# MCU.net
KiCad netlist of a schematic drawn in Altium Designer
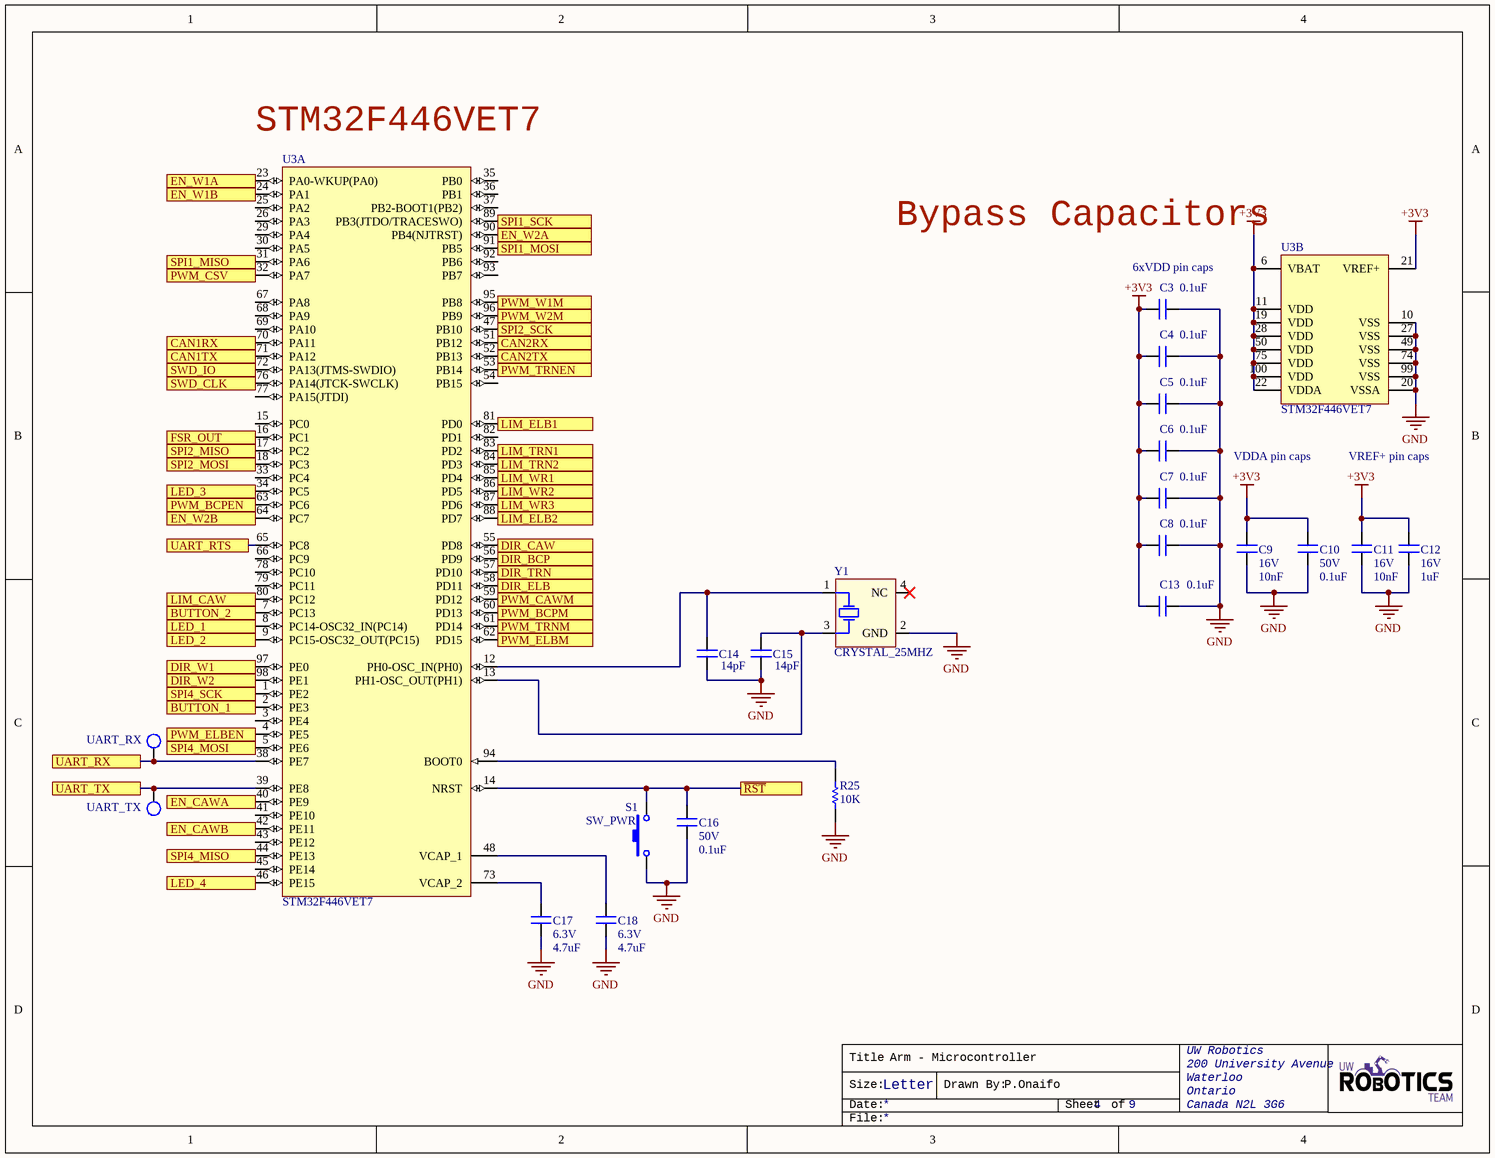
[diagram p0: MCU.SchDoc]

(export (version "E")
  (design (tool "Eeschema 10.0.6"))
  (components
    (comp (ref "C3")
      (value "0.1uF")
      (footprint "CAPC0603(1608)55_N")
      (description "CAP CER 0.1UF 50V X7R 0603")
      (fields (field (name "MPN") "CC0603KRX7R9BB104") (field (name "MANUFACTURER") "Yageo"))
      (libsource (lib "UWRT_Schematic_Library_2020") (part "CAP_0.1uF_50V_0603"))
    )
    (comp (ref "C4")
      (value "0.1uF")
      (footprint "CAPC0603(1608)55_N")
      (description "CAP CER 0.1UF 50V X7R 0603")
      (fields (field (name "MPN") "CC0603KRX7R9BB104") (field (name "MANUFACTURER") "Yageo"))
      (libsource (lib "UWRT_Schematic_Library_2020") (part "CAP_0.1uF_50V_0603"))
    )
    (comp (ref "C5")
      (value "0.1uF")
      (footprint "CAPC0603(1608)55_N")
      (description "CAP CER 0.1UF 50V X7R 0603")
      (fields (field (name "MPN") "CC0603KRX7R9BB104") (field (name "MANUFACTURER") "Yageo"))
      (libsource (lib "UWRT_Schematic_Library_2020") (part "CAP_0.1uF_50V_0603"))
    )
    (comp (ref "C6")
      (value "0.1uF")
      (footprint "CAPC0603(1608)55_N")
      (description "CAP CER 0.1UF 50V X7R 0603")
      (fields (field (name "MPN") "CC0603KRX7R9BB104") (field (name "MANUFACTURER") "Yageo"))
      (libsource (lib "UWRT_Schematic_Library_2020") (part "CAP_0.1uF_50V_0603"))
    )
    (comp (ref "C7")
      (value "0.1uF")
      (footprint "CAPC0603(1608)55_N")
      (description "CAP CER 0.1UF 50V X7R 0603")
      (fields (field (name "MPN") "CC0603KRX7R9BB104") (field (name "MANUFACTURER") "Yageo"))
      (libsource (lib "UWRT_Schematic_Library_2020") (part "CAP_0.1uF_50V_0603"))
    )
    (comp (ref "C8")
      (value "0.1uF")
      (footprint "CAPC0603(1608)55_N")
      (description "CAP CER 0.1UF 50V X7R 0603")
      (fields (field (name "MPN") "CC0603KRX7R9BB104") (field (name "MANUFACTURER") "Yageo"))
      (libsource (lib "UWRT_Schematic_Library_2020") (part "CAP_0.1uF_50V_0603"))
    )
    (comp (ref "C9")
      (value "10nF")
      (footprint "CAPC0603(1608)55_N")
      (description "CAP CER 10000PF 16V X7R 0603")
      (fields
        (field (name "MPN") "CC0603KRX7R7BB103")
        (field (name "MANUFACTURER") "Yageo")
        (field (name "VOLTAGE RATING") "16V")
      )
      (libsource (lib "UWRT_Schematic_Library_2020") (part "CAP_10nF_0603"))
    )
    (comp (ref "C10")
      (value "0.1uF")
      (footprint "CAPC0603(1608)55_N")
      (description "CAP CER 0.1UF 50V X7R 0603")
      (fields
        (field (name "MPN") "CC0603KRX7R9BB104")
        (field (name "MANUFACTURER") "Yageo")
        (field (name "VOLTAGE RATING") "50V")
      )
      (libsource (lib "UWRT_Schematic_Library_2020") (part "CAP_0.1uF_50V_0603"))
    )
    (comp (ref "C11")
      (value "10nF")
      (footprint "CAPC0603(1608)55_N")
      (description "CAP CER 10000PF 16V X7R 0603")
      (fields
        (field (name "MPN") "CC0603KRX7R7BB103")
        (field (name "MANUFACTURER") "Yageo")
        (field (name "VOLTAGE RATING") "16V")
      )
      (libsource (lib "UWRT_Schematic_Library_2020") (part "CAP_10nF_0603"))
    )
    (comp (ref "C12")
      (value "1uF")
      (footprint "CAPC0603(1608)55_N")
      (description "CAP CER 1UF 16V Y5V 0603")
      (fields
        (field (name "MPN") "CC0603ZRY5V7BB105")
        (field (name "MANUFACTURER") "Yageo")
        (field (name "VOLTAGE RATING") "16V")
      )
      (libsource (lib "UWRT_Schematic_Library_2020") (part "CAP_1uF_16V_0603"))
    )
    (comp (ref "C13")
      (value "0.1uF")
      (footprint "CAPC0603(1608)55_N")
      (description "CAP CER 0.1UF 50V X7R 0603")
      (fields (field (name "MPN") "CC0603KRX7R9BB104") (field (name "MANUFACTURER") "Yageo"))
      (libsource (lib "UWRT_Schematic_Library_2020") (part "CAP_0.1uF_50V_0603"))
    )
    (comp (ref "C14")
      (value "14pF")
      (description "CAP CER 14PF 50V C0G/NP0 0603")
      (fields (field (name "TOLERANCE") "5%") (field (name "Comment") "CAP_14pF_50V_0603"))
      (libsource (lib "UWRT_Schematic_Library_2020") (part "CAP_14pF_50V_0603"))
    )
    (comp (ref "C15")
      (value "14pF")
      (description "CAP CER 14PF 50V C0G/NP0 0603")
      (fields (field (name "TOLERANCE") "5%") (field (name "Comment") "CAP_14pF_50V_0603"))
      (libsource (lib "UWRT_Schematic_Library_2020") (part "CAP_14pF_50V_0603"))
    )
    (comp (ref "C16")
      (value "0.1uF")
      (footprint "CAPC0603(1608)55_N")
      (description "CAP CER 0.1UF 50V X7R 0603")
      (fields
        (field (name "MPN") "CC0603KRX7R9BB104")
        (field (name "MANUFACTURER") "Yageo")
        (field (name "VOLTAGE RATING") "50V")
      )
      (libsource (lib "UWRT_Schematic_Library_2020") (part "CAP_0.1uF_50V_0603"))
    )
    (comp (ref "C17")
      (value "4.7uF")
      (footprint "CAPC0603(1608)55_N")
      (description "CAP CER 4.7UF 6.3V X5R 0603")
      (fields
        (field (name "MPN") "CC0603KRX5R5BB475")
        (field (name "MANUFACTURER") "Yageo")
        (field (name "VOLTAGE RATING") "6.3V")
      )
      (libsource (lib "UWRT_Schematic_Library_2020") (part "CAP_4.7uF_0603"))
    )
    (comp (ref "C18")
      (value "4.7uF")
      (footprint "CAPC0603(1608)55_N")
      (description "CAP CER 4.7UF 6.3V X5R 0603")
      (fields
        (field (name "MPN") "CC0603KRX5R5BB475")
        (field (name "MANUFACTURER") "Yageo")
        (field (name "VOLTAGE RATING") "6.3V")
      )
      (libsource (lib "UWRT_Schematic_Library_2020") (part "CAP_4.7uF_0603"))
    )
    (comp (ref "R25")
      (value "10K")
      (footprint "RESC0603(1608)_N")
      (description "RES SMD 10K OHM 5% 1/10W 0603")
      (fields (field (name "MANUFACTURER") "Yageo") (field (name "MPN") "RC0603JR-0710KL"))
      (libsource (lib "UWRT_Schematic_Library_2020") (part "RES_10K_0603"))
    )
    (comp (ref "S1")
      (value "SW_PWR")
      (footprint "PTS830GM140")
      (description "Power Switch (Red)")
      (fields (field (name "MPN") "PTS830GM140 SMTR LFS") (field (name "MANUFACTURER") "C&K"))
      (libsource (lib "UWRT_Schematic_Library_2020") (part "SW_PWR"))
    )
    (comp (ref "U3")
      (value "STM32F446VET7")
      (footprint "STM-LQFP100_L")
      (libsource (lib "Altium Content Vault") (part "MC-ARM-STM32F446-LQFP100"))
    )
    (comp (ref "UART_RX")
      (value "TESTPOINT_LOOP")
      (footprint "TESTPOINT_LOOP")
      (description "Loop testpoint through-hole pad")
      (fields (field (name "MANUFACTURER") "Keystone Electronics"))
      (libsource (lib "UWRT_Schematic_Library_2020") (part "TESTPOINT_LOOP"))
    )
    (comp (ref "UART_TX")
      (value "TESTPOINT_LOOP")
      (footprint "TESTPOINT_LOOP")
      (description "Loop testpoint through-hole pad")
      (fields (field (name "MANUFACTURER") "Keystone Electronics"))
      (libsource (lib "UWRT_Schematic_Library_2020") (part "TESTPOINT_LOOP"))
    )
    (comp (ref "Y1")
      (value "CRYSTAL_25MHZ")
      (description "CRYSTAL 25.0000MHZ 12PF SMD")
      (libsource (lib "UWRT_Schematic_Library_2020") (part "CRYSTAL_25MHZ"))
    )
  )
  (nets
    (net (code "1") (name "+3V3") (class "Default")
      (node (ref "C10") (pin "2") (pinfunction "2_2") (pintype "passive"))
      (node (ref "C11") (pin "1") (pinfunction "1_1") (pintype "passive"))
      (node (ref "C12") (pin "2") (pinfunction "2_2") (pintype "passive"))
      (node (ref "C13") (pin "1") (pinfunction "1_1") (pintype "passive"))
      (node (ref "C3") (pin "1") (pinfunction "1_1") (pintype "passive"))
      (node (ref "C4") (pin "1") (pinfunction "1_1") (pintype "passive"))
      (node (ref "C5") (pin "1") (pinfunction "1_1") (pintype "passive"))
      (node (ref "C6") (pin "1") (pinfunction "1_1") (pintype "passive"))
      (node (ref "C7") (pin "1") (pinfunction "1_1") (pintype "passive"))
      (node (ref "C8") (pin "1") (pinfunction "1_1") (pintype "passive"))
      (node (ref "C9") (pin "2") (pinfunction "2_2") (pintype "passive"))
      (node (ref "U3") (pin "100") (pinfunction "VDD_100") (pintype "power_in"))
      (node (ref "U3") (pin "11") (pinfunction "VDD_11") (pintype "power_in"))
      (node (ref "U3") (pin "19") (pinfunction "VDD_19") (pintype "power_in"))
      (node (ref "U3") (pin "21") (pinfunction "VREF+_21") (pintype "power_in"))
      (node (ref "U3") (pin "22") (pinfunction "VDDA_22") (pintype "power_in"))
      (node (ref "U3") (pin "28") (pinfunction "VDD_28") (pintype "power_in"))
      (node (ref "U3") (pin "50") (pinfunction "VDD_50") (pintype "power_in"))
      (node (ref "U3") (pin "6") (pinfunction "VBAT_6") (pintype "power_in"))
      (node (ref "U3") (pin "75") (pinfunction "VDD_75") (pintype "power_in"))
    )
    (net (code "2") (name "/BUTTON_1") (class "Default")
      (node (ref "U3") (pin "2") (pinfunction "PE3_2") (pintype "bidirectional"))
    )
    (net (code "3") (name "/BUTTON_2") (class "Default")
      (node (ref "U3") (pin "7") (pinfunction "PC13_7") (pintype "bidirectional"))
    )
    (net (code "4") (name "/CAN1RX") (class "Default")
      (node (ref "U3") (pin "70") (pinfunction "PA11_70") (pintype "bidirectional"))
    )
    (net (code "5") (name "/CAN1TX") (class "Default")
      (node (ref "U3") (pin "71") (pinfunction "PA12_71") (pintype "bidirectional"))
    )
    (net (code "6") (name "/CAN2RX") (class "Default")
      (node (ref "U3") (pin "51") (pinfunction "PB12_51") (pintype "bidirectional"))
    )
    (net (code "7") (name "/CAN2TX") (class "Default")
      (node (ref "U3") (pin "52") (pinfunction "PB13_52") (pintype "bidirectional"))
    )
    (net (code "8") (name "/DIR_BCP") (class "Default")
      (node (ref "U3") (pin "56") (pinfunction "PD9_56") (pintype "bidirectional"))
    )
    (net (code "9") (name "/DIR_CAW") (class "Default")
      (node (ref "U3") (pin "55") (pinfunction "PD8_55") (pintype "bidirectional"))
    )
    (net (code "10") (name "/DIR_ELB") (class "Default")
      (node (ref "U3") (pin "58") (pinfunction "PD11_58") (pintype "bidirectional"))
    )
    (net (code "11") (name "/DIR_TRN") (class "Default")
      (node (ref "U3") (pin "57") (pinfunction "PD10_57") (pintype "bidirectional"))
    )
    (net (code "12") (name "/DIR_W1") (class "Default")
      (node (ref "U3") (pin "97") (pinfunction "PE0_97") (pintype "bidirectional"))
    )
    (net (code "13") (name "/DIR_W2") (class "Default")
      (node (ref "U3") (pin "98") (pinfunction "PE1_98") (pintype "bidirectional"))
    )
    (net (code "14") (name "/EN_CAWA") (class "Default")
      (node (ref "U3") (pin "40") (pinfunction "PE9_40") (pintype "bidirectional"))
    )
    (net (code "15") (name "/EN_CAWB") (class "Default")
      (node (ref "U3") (pin "42") (pinfunction "PE11_42") (pintype "bidirectional"))
    )
    (net (code "16") (name "/EN_W1A") (class "Default")
      (node (ref "U3") (pin "23") (pinfunction "PA0-WKUP(PA0)_23") (pintype "bidirectional"))
    )
    (net (code "17") (name "/EN_W1B") (class "Default")
      (node (ref "U3") (pin "24") (pinfunction "PA1_24") (pintype "bidirectional"))
    )
    (net (code "18") (name "/EN_W2A") (class "Default")
      (node (ref "U3") (pin "90") (pinfunction "PB4(NJTRST)_90") (pintype "bidirectional"))
    )
    (net (code "19") (name "/EN_W2B") (class "Default")
      (node (ref "U3") (pin "64") (pinfunction "PC7_64") (pintype "bidirectional"))
    )
    (net (code "20") (name "/FSR_OUT") (class "Default")
      (node (ref "U3") (pin "16") (pinfunction "PC1_16") (pintype "bidirectional"))
    )
    (net (code "21") (name "/LED_1") (class "Default")
      (node (ref "U3") (pin "8") (pinfunction "PC14-OSC32_IN(PC14)_8") (pintype "bidirectional"))
    )
    (net (code "22") (name "/LED_2") (class "Default")
      (node (ref "U3") (pin "9") (pinfunction "PC15-OSC32_OUT(PC15)_9") (pintype "bidirectional"))
    )
    (net (code "23") (name "/LED_3") (class "Default")
      (node (ref "U3") (pin "34") (pinfunction "PC5_34") (pintype "bidirectional"))
    )
    (net (code "24") (name "/LED_4") (class "Default")
      (node (ref "U3") (pin "46") (pinfunction "PE15_46") (pintype "bidirectional"))
    )
    (net (code "25") (name "/LIM_CAW") (class "Default")
      (node (ref "U3") (pin "80") (pinfunction "PC12_80") (pintype "bidirectional"))
    )
    (net (code "26") (name "/LIM_ELB1") (class "Default")
      (node (ref "U3") (pin "81") (pinfunction "PD0_81") (pintype "bidirectional"))
    )
    (net (code "27") (name "/LIM_ELB2") (class "Default")
      (node (ref "U3") (pin "88") (pinfunction "PD7_88") (pintype "bidirectional"))
    )
    (net (code "28") (name "/LIM_TRN1") (class "Default")
      (node (ref "U3") (pin "83") (pinfunction "PD2_83") (pintype "bidirectional"))
    )
    (net (code "29") (name "/LIM_TRN2") (class "Default")
      (node (ref "U3") (pin "84") (pinfunction "PD3_84") (pintype "bidirectional"))
    )
    (net (code "30") (name "/LIM_WR1") (class "Default")
      (node (ref "U3") (pin "85") (pinfunction "PD4_85") (pintype "bidirectional"))
    )
    (net (code "31") (name "/LIM_WR2") (class "Default")
      (node (ref "U3") (pin "86") (pinfunction "PD5_86") (pintype "bidirectional"))
    )
    (net (code "32") (name "/LIM_WR3") (class "Default")
      (node (ref "U3") (pin "87") (pinfunction "PD6_87") (pintype "bidirectional"))
    )
    (net (code "33") (name "/PWM_BCPEN") (class "Default")
      (node (ref "U3") (pin "63") (pinfunction "PC6_63") (pintype "bidirectional"))
    )
    (net (code "34") (name "/PWM_BCPM") (class "Default")
      (node (ref "U3") (pin "60") (pinfunction "PD13_60") (pintype "bidirectional"))
    )
    (net (code "35") (name "/PWM_CAWM") (class "Default")
      (node (ref "U3") (pin "59") (pinfunction "PD12_59") (pintype "bidirectional"))
    )
    (net (code "36") (name "/PWM_CSV") (class "Default")
      (node (ref "U3") (pin "32") (pinfunction "PA7_32") (pintype "bidirectional"))
    )
    (net (code "37") (name "/PWM_ELBEN") (class "Default")
      (node (ref "U3") (pin "4") (pinfunction "PE5_4") (pintype "bidirectional"))
    )
    (net (code "38") (name "/PWM_ELBM") (class "Default")
      (node (ref "U3") (pin "62") (pinfunction "PD15_62") (pintype "bidirectional"))
    )
    (net (code "39") (name "/PWM_TRNEN") (class "Default")
      (node (ref "U3") (pin "53") (pinfunction "PB14_53") (pintype "bidirectional"))
    )
    (net (code "40") (name "/PWM_TRNM") (class "Default")
      (node (ref "U3") (pin "61") (pinfunction "PD14_61") (pintype "bidirectional"))
    )
    (net (code "41") (name "/PWM_W1M") (class "Default")
      (node (ref "U3") (pin "95") (pinfunction "PB8_95") (pintype "bidirectional"))
    )
    (net (code "42") (name "/PWM_W2M") (class "Default")
      (node (ref "U3") (pin "96") (pinfunction "PB9_96") (pintype "bidirectional"))
    )
    (net (code "43") (name "/SPI1_MISO") (class "Default")
      (node (ref "U3") (pin "31") (pinfunction "PA6_31") (pintype "bidirectional"))
    )
    (net (code "44") (name "/SPI1_MOSI") (class "Default")
      (node (ref "U3") (pin "91") (pinfunction "PB5_91") (pintype "bidirectional"))
    )
    (net (code "45") (name "/SPI1_SCK") (class "Default")
      (node (ref "U3") (pin "89") (pinfunction "PB3(JTDO/TRACESWO)_89") (pintype "bidirectional"))
    )
    (net (code "46") (name "/SPI2_MISO") (class "Default")
      (node (ref "U3") (pin "17") (pinfunction "PC2_17") (pintype "bidirectional"))
    )
    (net (code "47") (name "/SPI2_MOSI") (class "Default")
      (node (ref "U3") (pin "18") (pinfunction "PC3_18") (pintype "bidirectional"))
    )
    (net (code "48") (name "/SPI2_SCK") (class "Default")
      (node (ref "U3") (pin "47") (pinfunction "PB10_47") (pintype "bidirectional"))
    )
    (net (code "49") (name "/SPI4_MISO") (class "Default")
      (node (ref "U3") (pin "44") (pinfunction "PE13_44") (pintype "bidirectional"))
    )
    (net (code "50") (name "/SPI4_MOSI") (class "Default")
      (node (ref "U3") (pin "5") (pinfunction "PE6_5") (pintype "bidirectional"))
    )
    (net (code "51") (name "/SPI4_SCK") (class "Default")
      (node (ref "U3") (pin "1") (pinfunction "PE2_1") (pintype "bidirectional"))
    )
    (net (code "52") (name "/SWD_CLK") (class "Default")
      (node (ref "U3") (pin "76") (pinfunction "PA14(JTCK-SWCLK)_76") (pintype "bidirectional"))
    )
    (net (code "53") (name "/SWD_IO") (class "Default")
      (node (ref "U3") (pin "72") (pinfunction "PA13(JTMS-SWDIO)_72") (pintype "bidirectional"))
    )
    (net (code "54") (name "/UART_RTS") (class "Default")
      (node (ref "U3") (pin "65") (pinfunction "PC8_65") (pintype "bidirectional"))
    )
    (net (code "55") (name "/UART_RX") (class "Default")
      (node (ref "U3") (pin "38") (pinfunction "PE7_38") (pintype "bidirectional"))
      (node (ref "UART_RX") (pin "1") (pintype "passive"))
    )
    (net (code "56") (name "/UART_TX") (class "Default")
      (node (ref "U3") (pin "39") (pinfunction "PE8_39") (pintype "bidirectional"))
      (node (ref "UART_TX") (pin "1") (pintype "passive"))
    )
    (net (code "57") (name "/~{RST}") (class "Default")
      (node (ref "C16") (pin "2") (pinfunction "2_2") (pintype "passive"))
      (node (ref "S1") (pin "2") (pinfunction "2_2") (pintype "passive"))
      (node (ref "U3") (pin "14") (pinfunction "NRST_14") (pintype "bidirectional"))
    )
    (net (code "58") (name "GND") (class "Default")
      (node (ref "C10") (pin "1") (pinfunction "1_1") (pintype "passive"))
      (node (ref "C11") (pin "2") (pinfunction "2_2") (pintype "passive"))
      (node (ref "C12") (pin "1") (pinfunction "1_1") (pintype "passive"))
      (node (ref "C13") (pin "2") (pinfunction "2_2") (pintype "passive"))
      (node (ref "C14") (pin "1") (pinfunction "1_1") (pintype "passive"))
      (node (ref "C15") (pin "1") (pinfunction "1_1") (pintype "passive"))
      (node (ref "C16") (pin "1") (pinfunction "1_1") (pintype "passive"))
      (node (ref "C17") (pin "1") (pinfunction "1_1") (pintype "passive"))
      (node (ref "C18") (pin "1") (pinfunction "1_1") (pintype "passive"))
      (node (ref "C3") (pin "2") (pinfunction "2_2") (pintype "passive"))
      (node (ref "C4") (pin "2") (pinfunction "2_2") (pintype "passive"))
      (node (ref "C5") (pin "2") (pinfunction "2_2") (pintype "passive"))
      (node (ref "C6") (pin "2") (pinfunction "2_2") (pintype "passive"))
      (node (ref "C7") (pin "2") (pinfunction "2_2") (pintype "passive"))
      (node (ref "C8") (pin "2") (pinfunction "2_2") (pintype "passive"))
      (node (ref "C9") (pin "1") (pinfunction "1_1") (pintype "passive"))
      (node (ref "R25") (pin "2") (pinfunction "2_2") (pintype "passive"))
      (node (ref "S1") (pin "1") (pinfunction "1_1") (pintype "passive"))
      (node (ref "U3") (pin "10") (pinfunction "VSS_10") (pintype "power_in"))
      (node (ref "U3") (pin "20") (pinfunction "VSSA_20") (pintype "power_in"))
      (node (ref "U3") (pin "27") (pinfunction "VSS_27") (pintype "power_in"))
      (node (ref "U3") (pin "49") (pinfunction "VSS_49") (pintype "power_in"))
      (node (ref "U3") (pin "74") (pinfunction "VSS_74") (pintype "power_in"))
      (node (ref "U3") (pin "99") (pinfunction "VSS_99") (pintype "power_in"))
      (node (ref "Y1") (pin "2") (pinfunction "GND_2") (pintype "power_in"))
    )
    (net (code "59") (name "Net-(U3A-BOOT0)") (class "Default")
      (node (ref "R25") (pin "1") (pinfunction "1_1") (pintype "passive"))
      (node (ref "U3") (pin "94") (pinfunction "BOOT0_94") (pintype "input"))
    )
    (net (code "60") (name "Net-(U3A-PH0-OSC_IN(PH0))") (class "Default")
      (node (ref "C14") (pin "2") (pinfunction "2_2") (pintype "passive"))
      (node (ref "U3") (pin "12") (pinfunction "PH0-OSC_IN(PH0)_12") (pintype "bidirectional"))
      (node (ref "Y1") (pin "1") (pinfunction "HOT_1") (pintype "passive"))
    )
    (net (code "61") (name "Net-(U3A-PH1-OSC_OUT(PH1))") (class "Default")
      (node (ref "C15") (pin "2") (pinfunction "2_2") (pintype "passive"))
      (node (ref "U3") (pin "13") (pinfunction "PH1-OSC_OUT(PH1)_13") (pintype "bidirectional"))
      (node (ref "Y1") (pin "3") (pinfunction "HOT_3") (pintype "passive"))
    )
    (net (code "62") (name "Net-(U3A-VCAP_1)") (class "Default")
      (node (ref "C18") (pin "2") (pinfunction "2_2") (pintype "passive"))
      (node (ref "U3") (pin "48") (pinfunction "VCAP_1_48") (pintype "passive"))
    )
    (net (code "63") (name "Net-(U3A-VCAP_2)") (class "Default")
      (node (ref "C17") (pin "2") (pinfunction "2_2") (pintype "passive"))
      (node (ref "U3") (pin "73") (pinfunction "VCAP_2_73") (pintype "passive"))
    )
    (net (code "64") (name "unconnected-(U3A-PA2-Pad25)") (class "Default")
      (node (ref "U3") (pin "25") (pinfunction "PA2_25") (pintype "bidirectional"))
    )
    (net (code "65") (name "unconnected-(U3A-PA3-Pad26)") (class "Default")
      (node (ref "U3") (pin "26") (pinfunction "PA3_26") (pintype "bidirectional"))
    )
    (net (code "66") (name "unconnected-(U3A-PA4-Pad29)") (class "Default")
      (node (ref "U3") (pin "29") (pinfunction "PA4_29") (pintype "bidirectional"))
    )
    (net (code "67") (name "unconnected-(U3A-PA5-Pad30)") (class "Default")
      (node (ref "U3") (pin "30") (pinfunction "PA5_30") (pintype "bidirectional"))
    )
    (net (code "68") (name "unconnected-(U3A-PA8-Pad67)") (class "Default")
      (node (ref "U3") (pin "67") (pinfunction "PA8_67") (pintype "bidirectional"))
    )
    (net (code "69") (name "unconnected-(U3A-PA9-Pad68)") (class "Default")
      (node (ref "U3") (pin "68") (pinfunction "PA9_68") (pintype "bidirectional"))
    )
    (net (code "70") (name "unconnected-(U3A-PA10-Pad69)") (class "Default")
      (node (ref "U3") (pin "69") (pinfunction "PA10_69") (pintype "bidirectional"))
    )
    (net (code "71") (name "unconnected-(U3A-PA15(JTDI)-Pad77)") (class "Default")
      (node (ref "U3") (pin "77") (pinfunction "PA15(JTDI)_77") (pintype "bidirectional"))
    )
    (net (code "72") (name "unconnected-(U3A-PB0-Pad35)") (class "Default")
      (node (ref "U3") (pin "35") (pinfunction "PB0_35") (pintype "bidirectional"))
    )
    (net (code "73") (name "unconnected-(U3A-PB1-Pad36)") (class "Default")
      (node (ref "U3") (pin "36") (pinfunction "PB1_36") (pintype "bidirectional"))
    )
    (net (code "74") (name "unconnected-(U3A-PB2-BOOT1(PB2)-Pad37)") (class "Default")
      (node (ref "U3") (pin "37") (pinfunction "PB2-BOOT1(PB2)_37") (pintype "bidirectional"))
    )
    (net (code "75") (name "unconnected-(U3A-PB6-Pad92)") (class "Default")
      (node (ref "U3") (pin "92") (pinfunction "PB6_92") (pintype "bidirectional"))
    )
    (net (code "76") (name "unconnected-(U3A-PB7-Pad93)") (class "Default")
      (node (ref "U3") (pin "93") (pinfunction "PB7_93") (pintype "bidirectional"))
    )
    (net (code "77") (name "unconnected-(U3A-PB15-Pad54)") (class "Default")
      (node (ref "U3") (pin "54") (pinfunction "PB15_54") (pintype "bidirectional"))
    )
    (net (code "78") (name "unconnected-(U3A-PC0-Pad15)") (class "Default")
      (node (ref "U3") (pin "15") (pinfunction "PC0_15") (pintype "bidirectional"))
    )
    (net (code "79") (name "unconnected-(U3A-PC4-Pad33)") (class "Default")
      (node (ref "U3") (pin "33") (pinfunction "PC4_33") (pintype "bidirectional"))
    )
    (net (code "80") (name "unconnected-(U3A-PC9-Pad66)") (class "Default")
      (node (ref "U3") (pin "66") (pinfunction "PC9_66") (pintype "bidirectional"))
    )
    (net (code "81") (name "unconnected-(U3A-PC10-Pad78)") (class "Default")
      (node (ref "U3") (pin "78") (pinfunction "PC10_78") (pintype "bidirectional"))
    )
    (net (code "82") (name "unconnected-(U3A-PC11-Pad79)") (class "Default")
      (node (ref "U3") (pin "79") (pinfunction "PC11_79") (pintype "bidirectional"))
    )
    (net (code "83") (name "unconnected-(U3A-PD1-Pad82)") (class "Default")
      (node (ref "U3") (pin "82") (pinfunction "PD1_82") (pintype "bidirectional"))
    )
    (net (code "84") (name "unconnected-(U3A-PE4-Pad3)") (class "Default")
      (node (ref "U3") (pin "3") (pinfunction "PE4_3") (pintype "bidirectional"))
    )
    (net (code "85") (name "unconnected-(U3A-PE10-Pad41)") (class "Default")
      (node (ref "U3") (pin "41") (pinfunction "PE10_41") (pintype "bidirectional"))
    )
    (net (code "86") (name "unconnected-(U3A-PE12-Pad43)") (class "Default")
      (node (ref "U3") (pin "43") (pinfunction "PE12_43") (pintype "bidirectional"))
    )
    (net (code "87") (name "unconnected-(U3A-PE14-Pad45)") (class "Default")
      (node (ref "U3") (pin "45") (pinfunction "PE14_45") (pintype "bidirectional"))
    )
    (net (code "88") (name "unconnected-(Y1-NC-Pad4)") (class "Default")
      (node (ref "Y1") (pin "4") (pinfunction "NC_4") (pintype "passive+no_connect"))
    )
  )
)
